# mosamp.net
KiCad netlist of a schematic drawn in EAGLE
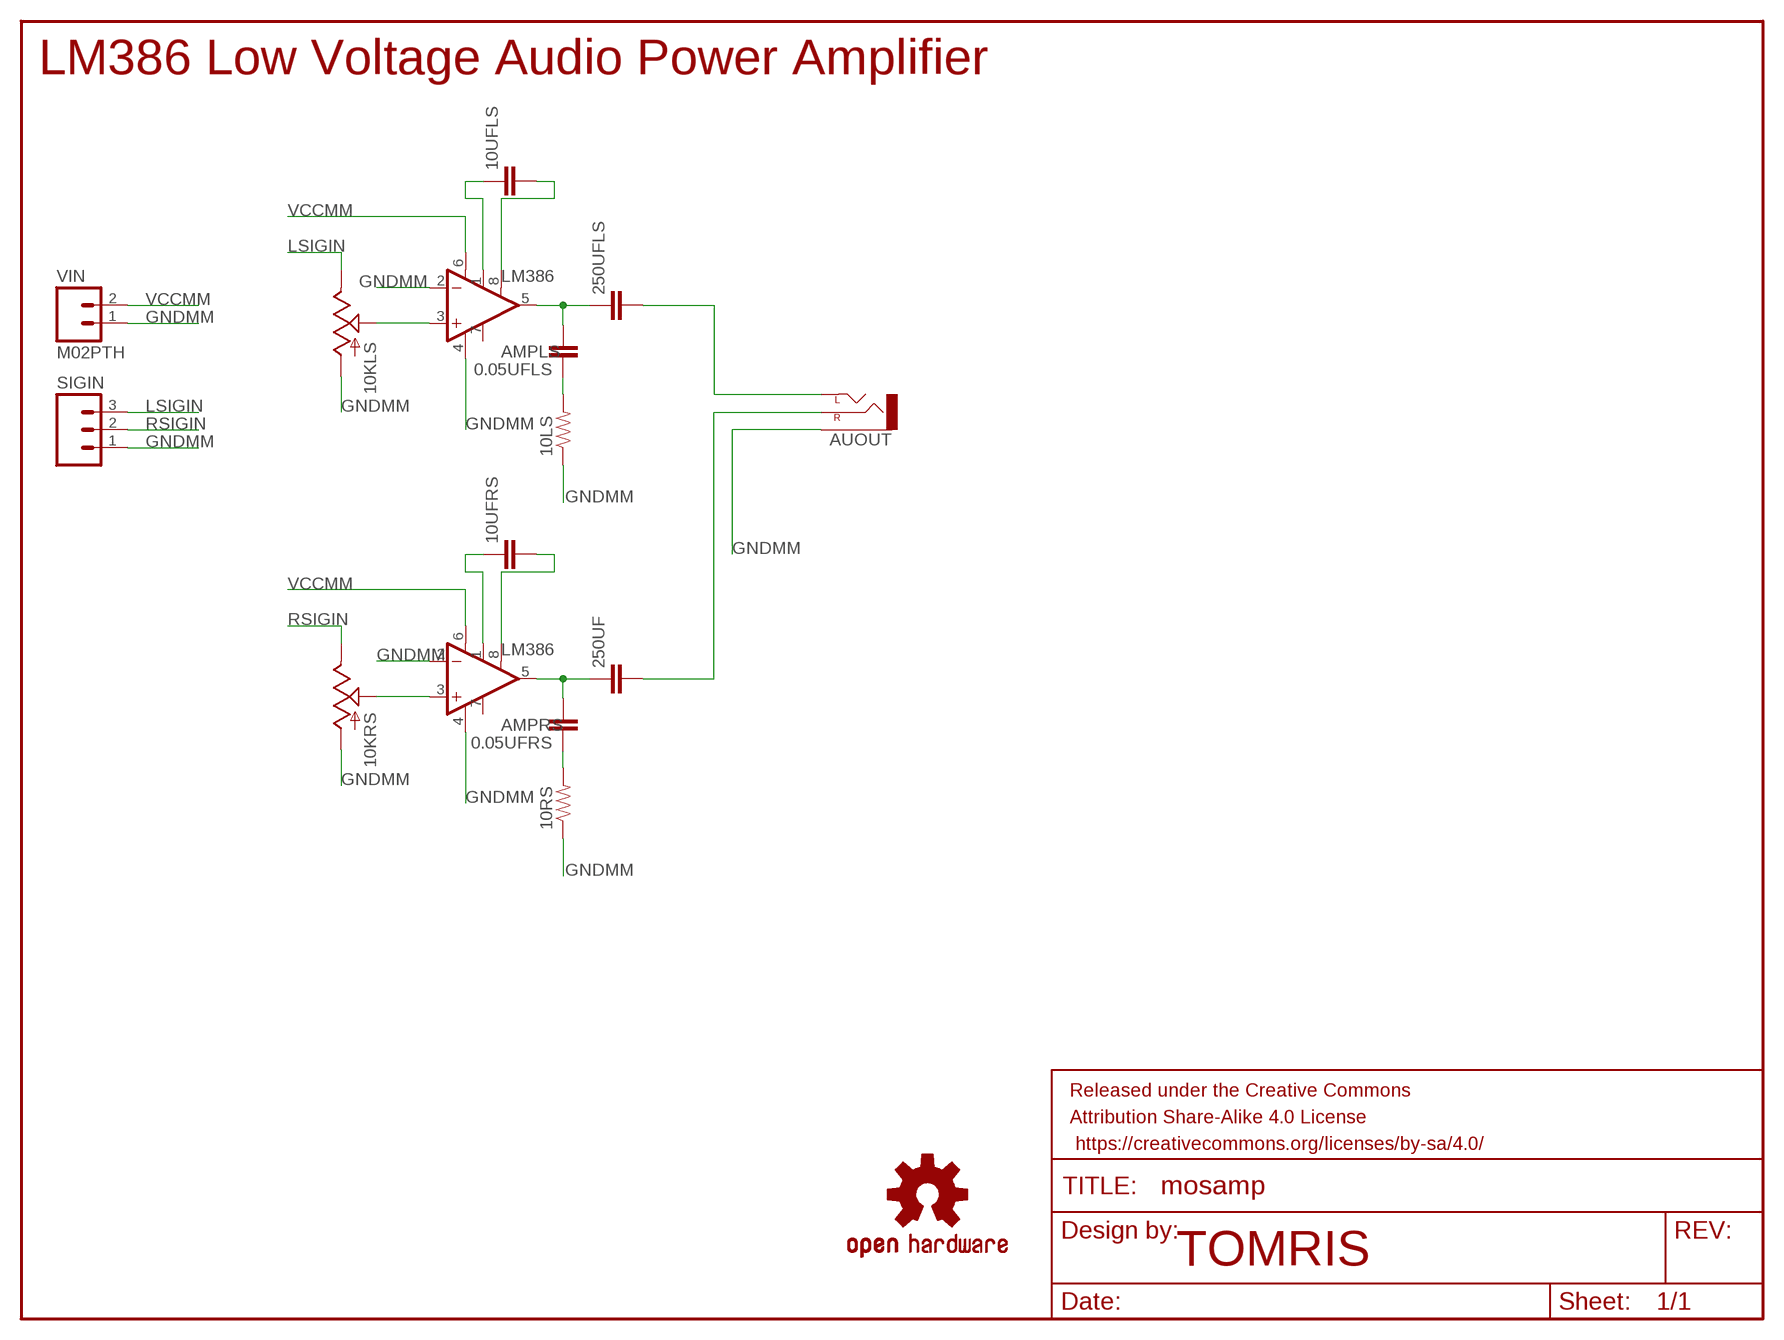
[diagram p0: schematic, sheet 1]

(export (version "E")
  (design (tool "Eeschema 10.0.6"))
  (components
    (comp (ref "0.05UFLS")
      (value "CAPPTH")
      (footprint "eagle-import:CAP-PTH-SMALL")
      (libsource (lib "eagle-import") (part "CAPPTH"))
    )
    (comp (ref "0.05UFRS")
      (value "CAPPTH")
      (footprint "eagle-import:CAP-PTH-SMALL")
      (libsource (lib "eagle-import") (part "CAPPTH"))
    )
    (comp (ref "10KLS")
      (value "POTMAM")
      (footprint "eagle-import:POT_MAMMOTH")
      (libsource (lib "eagle-import") (part "POTMAM"))
    )
    (comp (ref "10KRS")
      (value "POTMAM")
      (footprint "eagle-import:POT_MAMMOTH")
      (libsource (lib "eagle-import") (part "POTMAM"))
    )
    (comp (ref "10LS")
      (value "RESISTORAXIAL-0.3")
      (footprint "eagle-import:AXIAL-0.3")
      (libsource (lib "eagle-import") (part "RESISTORAXIAL-0.3"))
    )
    (comp (ref "10RS")
      (value "RESISTORAXIAL-0.3")
      (footprint "eagle-import:AXIAL-0.3")
      (libsource (lib "eagle-import") (part "RESISTORAXIAL-0.3"))
    )
    (comp (ref "10UFLS")
      (value "CAPPTH")
      (footprint "eagle-import:CAP-PTH-SMALL")
      (libsource (lib "eagle-import") (part "CAPPTH"))
    )
    (comp (ref "10UFRS")
      (value "CAPPTH")
      (footprint "eagle-import:CAP-PTH-SMALL")
      (libsource (lib "eagle-import") (part "CAPPTH"))
    )
    (comp (ref "250UF")
      (value "CAPPTH")
      (footprint "eagle-import:CAP-PTH-SMALL")
      (libsource (lib "eagle-import") (part "CAPPTH"))
    )
    (comp (ref "250UFLS")
      (value "CAPPTH")
      (footprint "eagle-import:CAP-PTH-SMALL")
      (libsource (lib "eagle-import") (part "CAPPTH"))
    )
    (comp (ref "AMPLS")
      (value "LM386")
      (footprint "eagle-import:DIP08")
      (libsource (lib "eagle-import") (part "LM386"))
    )
    (comp (ref "AMPRS")
      (value "LM386")
      (footprint "eagle-import:DIP08")
      (libsource (lib "eagle-import") (part "LM386"))
    )
    (comp (ref "AUOUT")
      (value "AUDIO-JACK2.5MM")
      (footprint "eagle-import:STEREOJACK2.5MM_STEREOJACK2.5MM")
      (libsource (lib "eagle-import") (part "AUDIO-JACK2.5MM"))
    )
    (comp (ref "FRAME1")
      (value "FRAME-LETTER")
      (footprint "eagle-import:CREATIVE_COMMONS")
      (libsource (lib "eagle-import") (part "FRAME-LETTER"))
    )
    (comp (ref "LOGO1")
      (value "OSHW-LOGOM")
      (footprint "eagle-import:OSHW-LOGO-M")
      (libsource (lib "eagle-import") (part "OSHW-LOGOM"))
    )
    (comp (ref "SIGIN")
      (value "M03PTH")
      (footprint "eagle-import:1X03")
      (libsource (lib "eagle-import") (part "M03PTH"))
    )
    (comp (ref "VIN")
      (value "M02PTH")
      (footprint "eagle-import:1X02")
      (libsource (lib "eagle-import") (part "M02PTH"))
    )
  )
  (nets
    (net (code "1") (name "/GNDMM") (class "Default")
      (node (ref "10KLS") (pin "P$2") (pinfunction "A_P$2") (pintype "passive"))
      (node (ref "10KRS") (pin "P$2") (pinfunction "A_P$2") (pintype "passive"))
      (node (ref "10LS") (pin "P$1") (pinfunction "1_P$1") (pintype "passive"))
      (node (ref "10RS") (pin "P$1") (pinfunction "1_P$1") (pintype "passive"))
      (node (ref "AMPLS") (pin "2") (pinfunction "-IN_2") (pintype "input"))
      (node (ref "AMPLS") (pin "4") (pinfunction "V-_4") (pintype "power_in"))
      (node (ref "AMPRS") (pin "2") (pinfunction "-IN_2") (pintype "input"))
      (node (ref "AMPRS") (pin "4") (pinfunction "V-_4") (pintype "power_in"))
      (node (ref "AUOUT") (pin "RING1") (pinfunction "SLEEVE_RING1") (pintype "bidirectional"))
      (node (ref "SIGIN") (pin "1") (pinfunction "1_1") (pintype "passive"))
      (node (ref "VIN") (pin "1") (pinfunction "1_1") (pintype "passive"))
    )
    (net (code "2") (name "/LSIGIN") (class "Default")
      (node (ref "10KLS") (pin "P$3") (pinfunction "E_P$3") (pintype "passive"))
      (node (ref "SIGIN") (pin "3") (pinfunction "3_3") (pintype "passive"))
    )
    (net (code "3") (name "/RSIGIN") (class "Default")
      (node (ref "10KRS") (pin "P$3") (pinfunction "E_P$3") (pintype "passive"))
      (node (ref "SIGIN") (pin "2") (pinfunction "2_2") (pintype "passive"))
    )
    (net (code "4") (name "/VCCMM") (class "Default")
      (node (ref "AMPLS") (pin "6") (pinfunction "V+_6") (pintype "power_in"))
      (node (ref "AMPRS") (pin "6") (pinfunction "V+_6") (pintype "power_in"))
      (node (ref "VIN") (pin "2") (pinfunction "2_2") (pintype "passive"))
    )
    (net (code "5") (name "Net-(10KLS-S)") (class "Default")
      (node (ref "10KLS") (pin "P$1") (pinfunction "S_P$1") (pintype "passive"))
      (node (ref "AMPLS") (pin "3") (pinfunction "+IN_3") (pintype "input"))
    )
    (net (code "6") (name "Net-(10KRS-S)") (class "Default")
      (node (ref "10KRS") (pin "P$1") (pinfunction "S_P$1") (pintype "passive"))
      (node (ref "AMPRS") (pin "3") (pinfunction "+IN_3") (pintype "input"))
    )
    (net (code "7") (name "Net-(10LS-2)") (class "Default")
      (node (ref "0.05UFLS") (pin "1") (pinfunction "1_1") (pintype "passive"))
      (node (ref "10LS") (pin "P$2") (pinfunction "2_P$2") (pintype "passive"))
    )
    (net (code "8") (name "Net-(10RS-2)") (class "Default")
      (node (ref "0.05UFRS") (pin "1") (pinfunction "1_1") (pintype "passive"))
      (node (ref "10RS") (pin "P$2") (pinfunction "2_P$2") (pintype "passive"))
    )
    (net (code "9") (name "Net-(10UFLS-Pad1)") (class "Default")
      (node (ref "10UFLS") (pin "1") (pinfunction "1_1") (pintype "passive"))
      (node (ref "AMPLS") (pin "1") (pinfunction "GAIN_1") (pintype "bidirectional"))
    )
    (net (code "10") (name "Net-(10UFLS-Pad2)") (class "Default")
      (node (ref "10UFLS") (pin "2") (pinfunction "2_2") (pintype "passive"))
      (node (ref "AMPLS") (pin "8") (pinfunction "GAIN_8") (pintype "bidirectional"))
    )
    (net (code "11") (name "Net-(10UFRS-Pad1)") (class "Default")
      (node (ref "10UFRS") (pin "1") (pinfunction "1_1") (pintype "passive"))
      (node (ref "AMPRS") (pin "1") (pinfunction "GAIN_1") (pintype "bidirectional"))
    )
    (net (code "12") (name "Net-(10UFRS-Pad2)") (class "Default")
      (node (ref "10UFRS") (pin "2") (pinfunction "2_2") (pintype "passive"))
      (node (ref "AMPRS") (pin "8") (pinfunction "GAIN_8") (pintype "bidirectional"))
    )
    (net (code "13") (name "Net-(AMPLS-OUT)") (class "Default")
      (node (ref "0.05UFLS") (pin "2") (pinfunction "2_2") (pintype "passive"))
      (node (ref "250UFLS") (pin "1") (pinfunction "1_1") (pintype "passive"))
      (node (ref "AMPLS") (pin "5") (pinfunction "OUT_5") (pintype "output"))
    )
    (net (code "14") (name "Net-(AMPRS-OUT)") (class "Default")
      (node (ref "0.05UFRS") (pin "2") (pinfunction "2_2") (pintype "passive"))
      (node (ref "250UF") (pin "1") (pinfunction "1_1") (pintype "passive"))
      (node (ref "AMPRS") (pin "5") (pinfunction "OUT_5") (pintype "output"))
    )
    (net (code "15") (name "Net-(AUOUT-LEFT)") (class "Default")
      (node (ref "250UFLS") (pin "2") (pinfunction "2_2") (pintype "passive"))
      (node (ref "AUOUT") (pin "SHIELD") (pinfunction "LEFT_SHIELD") (pintype "bidirectional"))
    )
    (net (code "16") (name "Net-(AUOUT-RIGHT)") (class "Default")
      (node (ref "250UF") (pin "2") (pinfunction "2_2") (pintype "passive"))
      (node (ref "AUOUT") (pin "TIP") (pinfunction "RIGHT_TIP") (pintype "bidirectional"))
    )
    (net (code "17") (name "unconnected-(AMPLS-BP-Pad7)") (class "Default")
      (node (ref "AMPLS") (pin "7") (pinfunction "BP_7") (pintype "bidirectional"))
    )
    (net (code "18") (name "unconnected-(AMPRS-BP-Pad7)") (class "Default")
      (node (ref "AMPRS") (pin "7") (pinfunction "BP_7") (pintype "bidirectional"))
    )
  )
)
